# Programming.net
KiCad netlist of a schematic drawn in Altium Designer
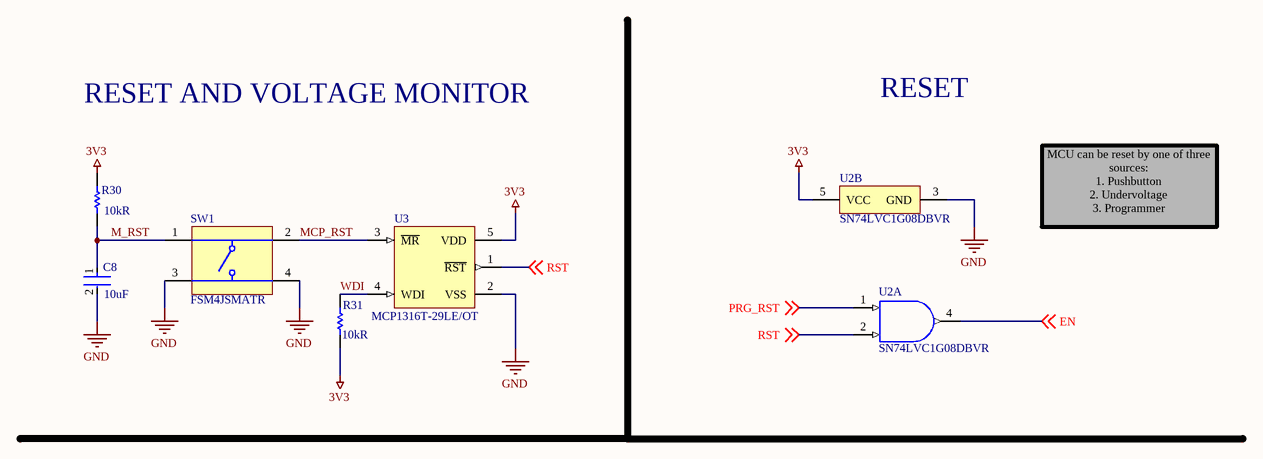
[diagram p0: Programming.SchDoc]

(export (version "E")
  (design (tool "Eeschema 10.0.6"))
  (components
    (comp (ref "C8")
      (value "10uF")
      (footprint "FP-C0805C-DG-MFG")
      (description "CAP CER 10UF 10V X5R 0805")
      (fields (field (name "TOLERANCE") "10%") (field (name "MANUFACTURER PART NUMBER") "C0805C106K8PACTU"))
      (libsource (lib "Altium Content Vault") (part "11868f565c42a9108669ba33697ecf6"))
    )
    (comp (ref "R30")
      (value "10kR")
      (footprint "RESC2013X60X35NL10T20")
      (description "Chip Resistor, 10 KOhm, +/- 1%, 0.125 W, -55 to 155 degC, 0805 (2012 Metric), RoHS, Tape and Reel")
      (fields
        (field (name "MANUFACTURER") "Yageo")
        (field (name "MANUFACTURER PART NUMBER") "RC0805FR-0710KL")
      )
      (libsource (lib "Altium Content Vault") (part "RES-2"))
    )
    (comp (ref "R31")
      (value "10kR")
      (footprint "RESC2013X60X35NL10T20")
      (description "Chip Resistor, 10 KOhm, +/- 1%, 0.125 W, -55 to 155 degC, 0805 (2012 Metric), RoHS, Tape and Reel")
      (fields
        (field (name "MANUFACTURER") "Yageo")
        (field (name "MANUFACTURER PART NUMBER") "RC0805FR-0710KL")
      )
      (libsource (lib "Altium Content Vault") (part "RES-2"))
    )
    (comp (ref "SW1")
      (value "FSM4JSMATR")
      (footprint "TECO-FSM4JSMATR_V")
      (description "Micro Miniature Push Button Switch FSM JSM, 50 mA, -35 to 85 degC, 4-Pin SMD, RoHS, Tape and Reel")
      (fields (field (name "MANUFACTURER") "TE Connectivity"))
      (libsource (lib "Altium Content Vault") (part "SW-SPST-4_A"))
    )
    (comp (ref "U2")
      (value "SN74LVC1G08DBVR")
      (footprint "DBV0005A_M")
      (description "Single 2-Input Positive-AND Gate, DBV0005A, LARGE T&R")
      (fields
        (field (name "GENERIC PART NUMBER") "SN74LVC1G08")
        (field (name "MANUFACTURER") "Texas Instruments")
      )
      (libsource (lib "Altium Content Vault") (part "TI-SN74XXX1X08-5"))
    )
    (comp (ref "U3")
      (value "MCP1316T-29LE/OT")
      (footprint "SOT-23-OT5_M")
      (description "Voltage Supervisor, 5-Pin SOT-23, Extended Temperature, Tape and Reel")
      (libsource (lib "Altium Content Vault") (part "PM-SCCT-MCP1316-5"))
    )
  )
  (nets
    (net (code "1") (name "/MCP_RST") (class "Default")
      (node (ref "SW1") (pin "2") (pinfunction "2_2") (pintype "passive"))
      (node (ref "U3") (pin "3") (pinfunction "~{MR}_3") (pintype "input"))
    )
    (net (code "2") (name "/M_RST") (class "Default")
      (node (ref "C8") (pin "1") (pinfunction "1_1") (pintype "passive"))
      (node (ref "R30") (pin "1") (pinfunction "1_1") (pintype "passive"))
      (node (ref "SW1") (pin "1") (pinfunction "1_1") (pintype "passive"))
    )
    (net (code "3") (name "/WDI") (class "Default")
      (node (ref "R31") (pin "2") (pinfunction "2_2") (pintype "passive"))
      (node (ref "U3") (pin "4") (pinfunction "WDI_4") (pintype "input"))
    )
    (net (code "4") (name "3V3") (class "Default")
      (node (ref "R30") (pin "2") (pinfunction "2_2") (pintype "passive"))
      (node (ref "R31") (pin "1") (pinfunction "1_1") (pintype "passive"))
      (node (ref "U2") (pin "5") (pinfunction "VCC_5") (pintype "power_in"))
      (node (ref "U3") (pin "5") (pinfunction "VDD_5") (pintype "power_in"))
    )
    (net (code "5") (name "EN") (class "Default")
      (node (ref "U2") (pin "4") (pinfunction "Y_4") (pintype "output"))
    )
    (net (code "6") (name "GND") (class "Default")
      (node (ref "C8") (pin "2") (pinfunction "2_2") (pintype "passive"))
      (node (ref "SW1") (pin "3") (pinfunction "3_3") (pintype "passive"))
      (node (ref "SW1") (pin "4") (pinfunction "4_4") (pintype "passive"))
      (node (ref "U2") (pin "3") (pinfunction "GND_3") (pintype "power_in"))
      (node (ref "U3") (pin "2") (pinfunction "VSS_2") (pintype "power_in"))
    )
    (net (code "7") (name "PRG_RST") (class "Default")
      (node (ref "U2") (pin "1") (pinfunction "A_1") (pintype "input"))
    )
    (net (code "8") (name "RST") (class "Default")
      (node (ref "U2") (pin "2") (pinfunction "B_2") (pintype "input"))
      (node (ref "U3") (pin "1") (pinfunction "~{RST}_1") (pintype "output"))
    )
  )
)
